# PWM_Driver.net
KiCad netlist of a schematic drawn in Altium Designer
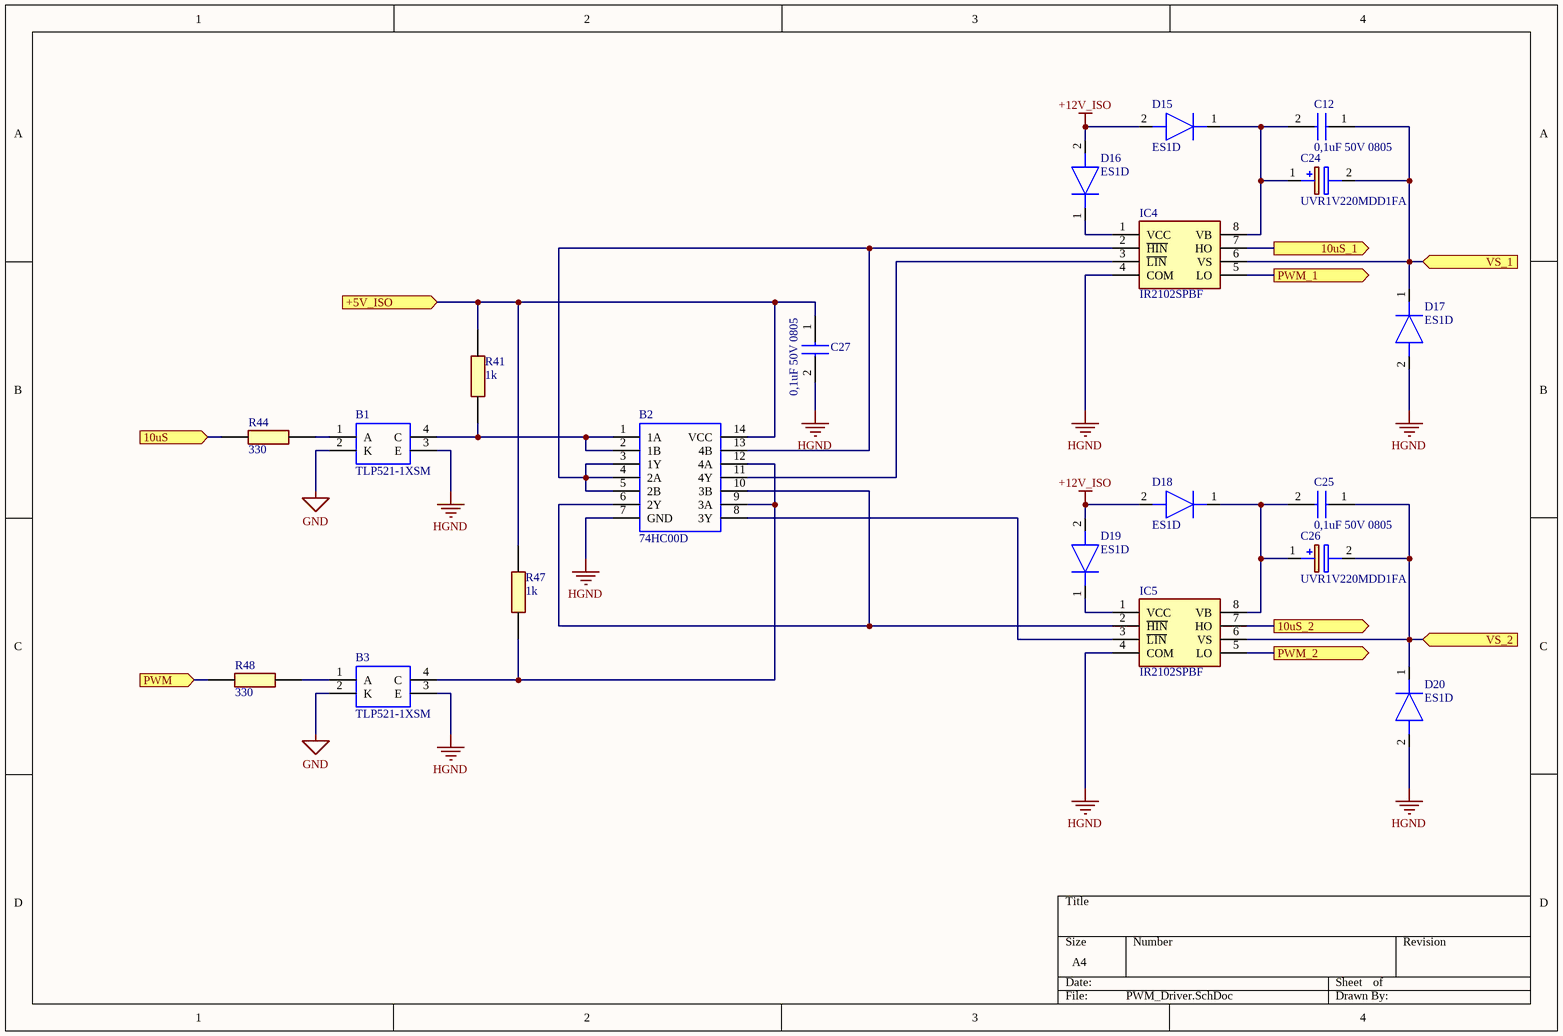
[diagram p0: PWM_Driver.SchDoc]

(export (version "E")
  (design (tool "Eeschema 10.0.6"))
  (components
    (comp (ref "B1")
      (value "TLP521-1XSM")
      (footprint "SOP254P1016X460-4N")
      (description "Optocoupler; SMD; Channels:1; Out: transistor; Uinsul:5.3kV")
      (libsource (lib "TLP521-1XSM") (part "TLP521-1XSM"))
    )
    (comp (ref "B2")
      (value "74HC00D")
      (footprint "SOIC127P600X175-14N")
      (description "NEXPERIA - 74HC00D - NAND Gate, 74HC00, 2 Input, 5.2 mA, 2 V to 6 V, SOIC-14")
      (fields (field (name "MOUSER PART NUMBER") "771-74HC00D"))
      (libsource (lib "74HC00D") (part "74HC00D"))
    )
    (comp (ref "B3")
      (value "TLP521-1XSM")
      (footprint "SOP254P1016X460-4N")
      (description "Optocoupler; SMD; Channels:1; Out: transistor; Uinsul:5.3kV")
      (libsource (lib "TLP521-1XSM") (part "TLP521-1XSM"))
    )
    (comp (ref "C12")
      (value "0,1uF 50V 0805")
      (footprint "SamacSys:CAPC2012X90N")
      (description "Capacitor")
      (libsource (lib "*") (part "MCMT21N470F250CT"))
    )
    (comp (ref "C24")
      (value "UVR1V220MDD1FA")
      (footprint "CAPPRD200W50D525H1250")
      (description "Capacitor Polarised")
      (fields (field (name "MOUSER PART NUMBER") "647-UVR1V220MDD1FA"))
      (libsource (lib "SamacSys") (part "UVR1V220MDD1FA"))
    )
    (comp (ref "C25")
      (value "0,1uF 50V 0805")
      (footprint "SamacSys:CAPC2012X90N")
      (description "Capacitor")
      (libsource (lib "*") (part "MCMT21N470F250CT"))
    )
    (comp (ref "C26")
      (value "UVR1V220MDD1FA")
      (footprint "CAPPRD200W50D525H1250")
      (description "Capacitor Polarised")
      (fields (field (name "MOUSER PART NUMBER") "647-UVR1V220MDD1FA"))
      (libsource (lib "SamacSys") (part "UVR1V220MDD1FA"))
    )
    (comp (ref "C27")
      (value "0,1uF 50V 0805")
      (footprint "SamacSys:CAPC2012X90N")
      (description "Capacitor")
      (libsource (lib "*") (part "MCMT21N470F250CT"))
    )
    (comp (ref "D15")
      (value "ES1D")
      (footprint "SamacSys:DIOM5226X295N")
      (description "Diode")
      (libsource (lib "SamacSys") (part "ES1D"))
    )
    (comp (ref "D16")
      (value "ES1D")
      (footprint "SamacSys:DIOM5226X295N")
      (description "Diode")
      (libsource (lib "SamacSys") (part "ES1D"))
    )
    (comp (ref "D17")
      (value "ES1D")
      (footprint "SamacSys:DIOM5226X295N")
      (description "Diode")
      (libsource (lib "SamacSys") (part "ES1D"))
    )
    (comp (ref "D18")
      (value "ES1D")
      (footprint "SamacSys:DIOM5226X295N")
      (description "Diode")
      (libsource (lib "SamacSys") (part "ES1D"))
    )
    (comp (ref "D19")
      (value "ES1D")
      (footprint "SamacSys:DIOM5226X295N")
      (description "Diode")
      (libsource (lib "SamacSys") (part "ES1D"))
    )
    (comp (ref "D20")
      (value "ES1D")
      (footprint "SamacSys:DIOM5226X295N")
      (description "Diode")
      (libsource (lib "SamacSys") (part "ES1D"))
    )
    (comp (ref "IC4")
      (value "IR2102SPBF")
      (footprint "SamacSys:SOIC127P600X175-8N")
      (description "Integrated Circuit")
      (fields (field (name "MOUSER PART NUMBER") "942-IR2102SPBF"))
      (libsource (lib "*") (part "IR2102SPBF"))
    )
    (comp (ref "IC5")
      (value "IR2102SPBF")
      (footprint "SamacSys:SOIC127P600X175-8N")
      (description "Integrated Circuit")
      (fields (field (name "MOUSER PART NUMBER") "942-IR2102SPBF"))
      (libsource (lib "*") (part "IR2102SPBF"))
    )
    (comp (ref "R41")
      (value "1k")
      (footprint "RESC2013X65N")
      (description "Resistor")
      (libsource (lib "SamacSys") (part "ERJP06J822V"))
    )
    (comp (ref "R44")
      (value "330")
      (footprint "RESC2013X65N")
      (description "Resistor")
      (libsource (lib "") (part "ERJP06J822V_1"))
    )
    (comp (ref "R47")
      (value "1k")
      (footprint "RESC2013X65N")
      (description "Resistor")
      (libsource (lib "SamacSys") (part "ERJP06J822V"))
    )
    (comp (ref "R48")
      (value "330")
      (footprint "RESC2013X65N")
      (description "Resistor")
      (libsource (lib "") (part "ERJP06J822V_1"))
    )
  )
  (nets
    (net (code "1") (name "+12V_ISO") (class "Default")
      (node (ref "D15") (pin "2") (pinfunction "A_2") (pintype "passive"))
      (node (ref "D16") (pin "2") (pinfunction "A_2") (pintype "passive"))
      (node (ref "D18") (pin "2") (pinfunction "A_2") (pintype "passive"))
      (node (ref "D19") (pin "2") (pinfunction "A_2") (pintype "passive"))
    )
    (net (code "2") (name "/+5V_ISO") (class "Default")
      (node (ref "B2") (pin "14") (pinfunction "VCC_14") (pintype "passive"))
      (node (ref "C27") (pin "1") (pinfunction "1_1") (pintype "passive"))
      (node (ref "R41") (pin "1") (pinfunction "1_1") (pintype "passive"))
      (node (ref "R47") (pin "1") (pinfunction "1_1") (pintype "passive"))
    )
    (net (code "3") (name "/10uS") (class "Default")
      (node (ref "R44") (pin "1") (pinfunction "1_1") (pintype "passive"))
    )
    (net (code "4") (name "/10uS_1") (class "Default")
      (node (ref "IC4") (pin "7") (pinfunction "HO_7") (pintype "passive"))
    )
    (net (code "5") (name "/10uS_2") (class "Default")
      (node (ref "IC5") (pin "7") (pinfunction "HO_7") (pintype "passive"))
    )
    (net (code "6") (name "/PWM") (class "Default")
      (node (ref "R48") (pin "1") (pinfunction "1_1") (pintype "passive"))
    )
    (net (code "7") (name "/PWM_1") (class "Default")
      (node (ref "IC4") (pin "5") (pinfunction "LO_5") (pintype "passive"))
    )
    (net (code "8") (name "/PWM_2") (class "Default")
      (node (ref "IC5") (pin "5") (pinfunction "LO_5") (pintype "passive"))
    )
    (net (code "9") (name "/VS_1") (class "Default")
      (node (ref "C12") (pin "1") (pinfunction "1_1") (pintype "passive"))
      (node (ref "C24") (pin "2") (pinfunction "-_2") (pintype "passive"))
      (node (ref "D17") (pin "1") (pinfunction "K_1") (pintype "passive"))
      (node (ref "IC4") (pin "6") (pinfunction "VS_6") (pintype "passive"))
    )
    (net (code "10") (name "/VS_2") (class "Default")
      (node (ref "C25") (pin "1") (pinfunction "1_1") (pintype "passive"))
      (node (ref "C26") (pin "2") (pinfunction "-_2") (pintype "passive"))
      (node (ref "D20") (pin "1") (pinfunction "K_1") (pintype "passive"))
      (node (ref "IC5") (pin "6") (pinfunction "VS_6") (pintype "passive"))
    )
    (net (code "11") (name "GND") (class "Default")
      (node (ref "B1") (pin "2") (pinfunction "K_2") (pintype "passive"))
      (node (ref "B3") (pin "2") (pinfunction "K_2") (pintype "passive"))
    )
    (net (code "12") (name "HGND") (class "Default")
      (node (ref "B1") (pin "3") (pinfunction "E_3") (pintype "passive"))
      (node (ref "B2") (pin "7") (pinfunction "GND_7") (pintype "passive"))
      (node (ref "B3") (pin "3") (pinfunction "E_3") (pintype "passive"))
      (node (ref "C27") (pin "2") (pinfunction "2_2") (pintype "passive"))
      (node (ref "D17") (pin "2") (pinfunction "A_2") (pintype "passive"))
      (node (ref "D20") (pin "2") (pinfunction "A_2") (pintype "passive"))
      (node (ref "IC4") (pin "4") (pinfunction "COM_4") (pintype "passive"))
      (node (ref "IC5") (pin "4") (pinfunction "COM_4") (pintype "passive"))
    )
    (net (code "13") (name "Net-(B1-A)") (class "Default")
      (node (ref "B1") (pin "1") (pinfunction "A_1") (pintype "passive"))
      (node (ref "R44") (pin "2") (pinfunction "2_2") (pintype "passive"))
    )
    (net (code "14") (name "Net-(B1-C)") (class "Default")
      (node (ref "B1") (pin "4") (pinfunction "C_4") (pintype "passive"))
      (node (ref "B2") (pin "1") (pinfunction "1A_1") (pintype "passive"))
      (node (ref "B2") (pin "2") (pinfunction "1B_2") (pintype "passive"))
      (node (ref "R41") (pin "2") (pinfunction "2_2") (pintype "passive"))
    )
    (net (code "15") (name "Net-(B2-1Y)") (class "Default")
      (node (ref "B2") (pin "13") (pinfunction "4B_13") (pintype "passive"))
      (node (ref "B2") (pin "3") (pinfunction "1Y_3") (pintype "passive"))
      (node (ref "B2") (pin "4") (pinfunction "2A_4") (pintype "passive"))
      (node (ref "B2") (pin "5") (pinfunction "2B_5") (pintype "passive"))
      (node (ref "IC4") (pin "2") (pinfunction "~{HIN}_2") (pintype "passive"))
    )
    (net (code "16") (name "Net-(B2-2Y)") (class "Default")
      (node (ref "B2") (pin "10") (pinfunction "3B_10") (pintype "passive"))
      (node (ref "B2") (pin "6") (pinfunction "2Y_6") (pintype "passive"))
      (node (ref "IC5") (pin "2") (pinfunction "~{HIN}_2") (pintype "passive"))
    )
    (net (code "17") (name "Net-(B2-3A)") (class "Default")
      (node (ref "B2") (pin "12") (pinfunction "4A_12") (pintype "passive"))
      (node (ref "B2") (pin "9") (pinfunction "3A_9") (pintype "passive"))
      (node (ref "B3") (pin "4") (pinfunction "C_4") (pintype "passive"))
      (node (ref "R47") (pin "2") (pinfunction "2_2") (pintype "passive"))
    )
    (net (code "18") (name "Net-(B2-3Y)") (class "Default")
      (node (ref "B2") (pin "8") (pinfunction "3Y_8") (pintype "passive"))
      (node (ref "IC5") (pin "3") (pinfunction "~{LIN}_3") (pintype "passive"))
    )
    (net (code "19") (name "Net-(B2-4Y)") (class "Default")
      (node (ref "B2") (pin "11") (pinfunction "4Y_11") (pintype "passive"))
      (node (ref "IC4") (pin "3") (pinfunction "~{LIN}_3") (pintype "passive"))
    )
    (net (code "20") (name "Net-(B3-A)") (class "Default")
      (node (ref "B3") (pin "1") (pinfunction "A_1") (pintype "passive"))
      (node (ref "R48") (pin "2") (pinfunction "2_2") (pintype "passive"))
    )
    (net (code "21") (name "Net-(C24-+)") (class "Default")
      (node (ref "C12") (pin "2") (pinfunction "2_2") (pintype "passive"))
      (node (ref "C24") (pin "1") (pinfunction "+_1") (pintype "passive"))
      (node (ref "D15") (pin "1") (pinfunction "K_1") (pintype "passive"))
      (node (ref "IC4") (pin "8") (pinfunction "VB_8") (pintype "passive"))
    )
    (net (code "22") (name "Net-(C26-+)") (class "Default")
      (node (ref "C25") (pin "2") (pinfunction "2_2") (pintype "passive"))
      (node (ref "C26") (pin "1") (pinfunction "+_1") (pintype "passive"))
      (node (ref "D18") (pin "1") (pinfunction "K_1") (pintype "passive"))
      (node (ref "IC5") (pin "8") (pinfunction "VB_8") (pintype "passive"))
    )
    (net (code "23") (name "Net-(D16-K)") (class "Default")
      (node (ref "D16") (pin "1") (pinfunction "K_1") (pintype "passive"))
      (node (ref "IC4") (pin "1") (pinfunction "VCC_1") (pintype "passive"))
    )
    (net (code "24") (name "Net-(D19-K)") (class "Default")
      (node (ref "D19") (pin "1") (pinfunction "K_1") (pintype "passive"))
      (node (ref "IC5") (pin "1") (pinfunction "VCC_1") (pintype "passive"))
    )
  )
)
